# LPCB218_-_INTERNAL_PRESSURE.net
KiCad netlist of a schematic drawn in Altium Designer
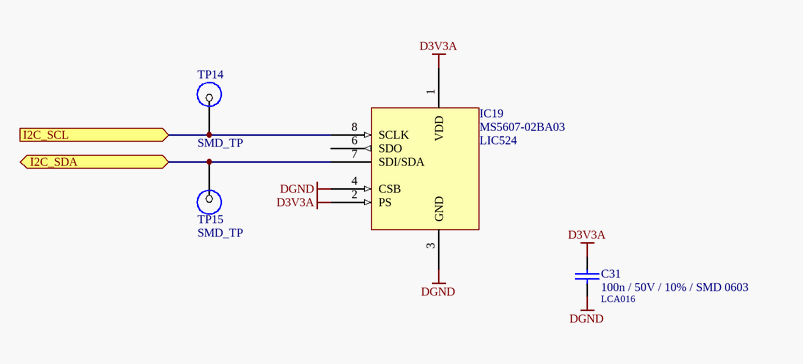
[diagram p0: LPCB218 - INTERNAL PRESSURE.SchDoc]

(export (version "E")
  (design (tool "Eeschema 10.0.6"))
  (components
    (comp (ref "C31")
      (value "100n / 50V / 10% / SMD 0603")
      (footprint "LFP011__CC1608-0603-IPC7351_B")
      (description "Capacitor, Ceramic Chip, 100nF (0.1uF), 50V, 5%, SMD 0603 [LCA016]")
      (fields (field (name "LDL_NUMBER") "LCA016"))
      (libsource (lib "LDL_Capacitors") (part "100n / 50V / 10% / SMD 0603"))
    )
    (comp (ref "IC19")
      (value "MS5607-02BA03")
      (footprint "LFP140__QFN8")
      (description "IC, Pressure Sensor IC, SMD QFN8 [LIC524]")
      (fields (field (name "LDL_NUMBER") "LIC524"))
      (libsource (lib "LDL_Semiconductors") (part "MS5607-02BA03"))
    )
    (comp (ref "TP14")
      (value "SMD_TP")
      (footprint "SMD-TP")
      (description "SMD Test Point")
      (libsource (lib "LDL_Connectors") (part "SMD_TP"))
    )
    (comp (ref "TP15")
      (value "SMD_TP")
      (footprint "SMD-TP")
      (description "SMD Test Point")
      (libsource (lib "LDL_Connectors") (part "SMD_TP"))
    )
  )
  (nets
    (net (code "1") (name "/I2C_SCL") (class "Default")
      (node (ref "IC19") (pin "8") (pinfunction "SCLK_8") (pintype "input"))
      (node (ref "TP14") (pin "1") (pintype "passive"))
    )
    (net (code "2") (name "/I2C_SDA") (class "Default")
      (node (ref "IC19") (pin "7") (pinfunction "SDI/SDA_7") (pintype "passive"))
      (node (ref "TP15") (pin "1") (pintype "passive"))
    )
    (net (code "3") (name "D3V3A") (class "Default")
      (node (ref "C31") (pin "1") (pintype "passive"))
      (node (ref "IC19") (pin "1") (pinfunction "VDD_1") (pintype "power_in"))
      (node (ref "IC19") (pin "2") (pinfunction "PS_2") (pintype "input"))
    )
    (net (code "4") (name "DGND") (class "Default")
      (node (ref "C31") (pin "2") (pintype "passive"))
      (node (ref "IC19") (pin "3") (pinfunction "GND_3") (pintype "power_in"))
      (node (ref "IC19") (pin "4") (pinfunction "CSB_4") (pintype "input"))
    )
    (net (code "5") (name "unconnected-(IC19-SDO-Pad6)") (class "Default")
      (node (ref "IC19") (pin "6") (pinfunction "SDO_6") (pintype "output"))
    )
  )
)
